# Periph.net
KiCad netlist of a schematic drawn in Altium Designer
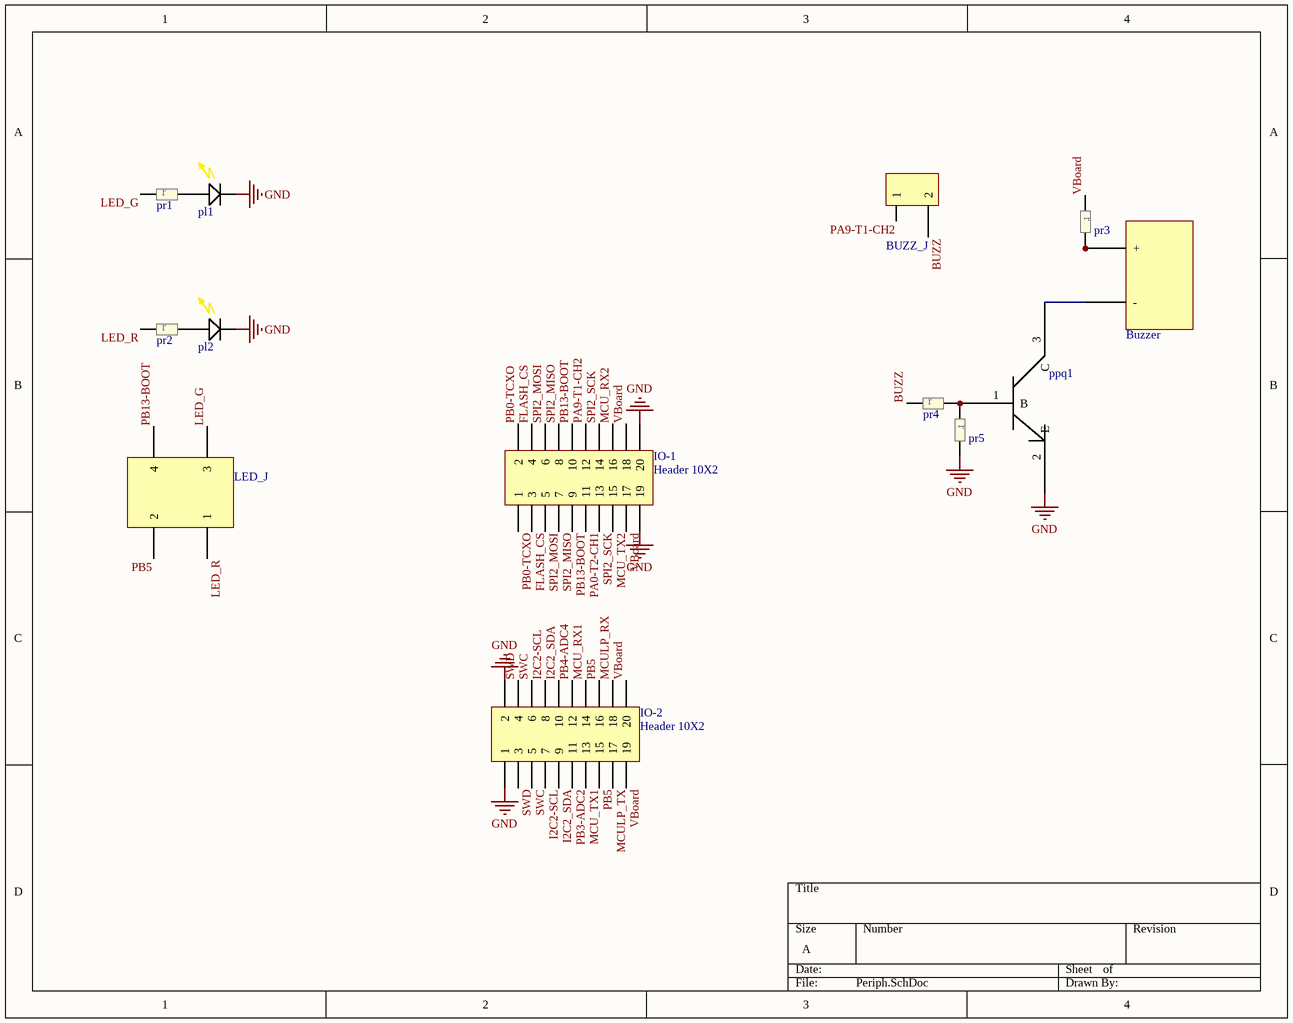
[diagram p0: Periph.SchDoc]

(export (version "E")
  (design (tool "Eeschema 10.0.6"))
  (components
    (comp (ref "Buzzer")
      (value "LED")
      (footprint "ABR_BUZZER_9MM_3D")
      (libsource (lib "abr_led_dip") (part "abr_buzzer"))
    )
    (comp (ref "BUZZ_J")
      (value "pin header 2mm")
      (footprint "abr_ph_2x1_2mm_3d_male")
      (libsource (lib "abr_ph_2mm_96_02") (part "abr_2x1_2mm"))
    )
    (comp (ref "IO-1")
      (value "Header 10X2")
      (footprint "HDR2X10")
      (description "Header, 10-Pin, Dual row")
      (fields (field (name "PUBLISHER") "Altium Limited"))
      (libsource (lib "Miscellaneous Connectors") (part "Header 10X2"))
    )
    (comp (ref "IO-2")
      (value "Header 10X2")
      (footprint "HDR2X10")
      (description "Header, 10-Pin, Dual row")
      (fields (field (name "PUBLISHER") "Altium Limited"))
      (libsource (lib "Miscellaneous Connectors") (part "Header 10X2"))
    )
    (comp (ref "LED_J")
      (value "pin header 2mm")
      (footprint "abr_ph_2x2_2mm_3d_male")
      (libsource (lib "abr_ph_2mm_96_02") (part "abr_2x2_2mm"))
    )
    (comp (ref "pl1")
      (value "smd-0805")
      (footprint "abr_led_g_0805_3d")
      (libsource (lib "abr_smd_0805_all") (part "abr_led_0805"))
    )
    (comp (ref "pl2")
      (value "smd-0805")
      (footprint "abr_led_r_0805_3d")
      (libsource (lib "abr_smd_0805_all") (part "abr_led_0805"))
    )
    (comp (ref "ppq1")
      (value "transistor")
      (footprint "abr_fp_sot-23_3d")
      (libsource (lib "abr_transistor_smd") (part "abr_bc847"))
    )
    (comp (ref "pr1")
      (value "2.2K")
      (footprint "abr_res_0805_3d")
      (libsource (lib "") (part "abr_res_0805_1"))
    )
    (comp (ref "pr2")
      (value "2.2K")
      (footprint "abr_res_0805_3d")
      (libsource (lib "") (part "abr_res_0805_1"))
    )
    (comp (ref "pr3")
      (value "2.2K")
      (footprint "abr_res_0805_3d")
      (libsource (lib "abr_smd_0805_all") (part "abr_res_0805"))
    )
    (comp (ref "pr4")
      (value "2.2K")
      (footprint "abr_res_0805_3d")
      (libsource (lib "") (part "abr_res_0805_1"))
    )
    (comp (ref "pr5")
      (value "2.2K")
      (footprint "abr_res_0805_3d")
      (libsource (lib "abr_smd_0805_all") (part "abr_res_0805"))
    )
  )
  (nets
    (net (code "1") (name "/BUZZ") (class "Default")
      (node (ref "BUZZ_J") (pin "2") (pinfunction "2_2") (pintype "passive"))
      (node (ref "pr4") (pin "0") (pinfunction "0_0") (pintype "passive"))
    )
    (net (code "2") (name "/FLASH_CS") (class "Default")
      (node (ref "IO-1") (pin "3") (pinfunction "3_3") (pintype "passive"))
      (node (ref "IO-1") (pin "4") (pinfunction "4_4") (pintype "passive"))
    )
    (net (code "3") (name "/I2C2-SCL") (class "Default")
      (node (ref "IO-2") (pin "7") (pinfunction "7_7") (pintype "passive"))
      (node (ref "IO-2") (pin "8") (pinfunction "8_8") (pintype "passive"))
    )
    (net (code "4") (name "/I2C2_SDA") (class "Default")
      (node (ref "IO-2") (pin "10") (pinfunction "10_10") (pintype "passive"))
      (node (ref "IO-2") (pin "9") (pinfunction "9_9") (pintype "passive"))
    )
    (net (code "5") (name "/LED_G") (class "Default")
      (node (ref "LED_J") (pin "3") (pinfunction "3_3") (pintype "passive"))
      (node (ref "pr1") (pin "0") (pinfunction "0_0") (pintype "passive"))
    )
    (net (code "6") (name "/LED_R") (class "Default")
      (node (ref "LED_J") (pin "1") (pinfunction "1_1") (pintype "passive"))
      (node (ref "pr2") (pin "0") (pinfunction "0_0") (pintype "passive"))
    )
    (net (code "7") (name "/MCULP_RX") (class "Default")
      (node (ref "IO-2") (pin "18") (pinfunction "18_18") (pintype "passive"))
    )
    (net (code "8") (name "/MCULP_TX") (class "Default")
      (node (ref "IO-2") (pin "17") (pinfunction "17_17") (pintype "passive"))
    )
    (net (code "9") (name "/MCU_RX1") (class "Default")
      (node (ref "IO-2") (pin "14") (pinfunction "14_14") (pintype "passive"))
    )
    (net (code "10") (name "/MCU_RX2") (class "Default")
      (node (ref "IO-1") (pin "16") (pinfunction "16_16") (pintype "passive"))
    )
    (net (code "11") (name "/MCU_TX1") (class "Default")
      (node (ref "IO-2") (pin "13") (pinfunction "13_13") (pintype "passive"))
    )
    (net (code "12") (name "/MCU_TX2") (class "Default")
      (node (ref "IO-1") (pin "15") (pinfunction "15_15") (pintype "passive"))
    )
    (net (code "13") (name "/PA0-T2-CH1") (class "Default")
      (node (ref "IO-1") (pin "11") (pinfunction "11_11") (pintype "passive"))
    )
    (net (code "14") (name "/PA9-T1-CH2") (class "Default")
      (node (ref "BUZZ_J") (pin "1") (pinfunction "1_1") (pintype "passive"))
      (node (ref "IO-1") (pin "12") (pinfunction "12_12") (pintype "passive"))
    )
    (net (code "15") (name "/PB0-TCXO") (class "Default")
      (node (ref "IO-1") (pin "1") (pinfunction "1_1") (pintype "passive"))
      (node (ref "IO-1") (pin "2") (pinfunction "2_2") (pintype "passive"))
    )
    (net (code "16") (name "/PB3-ADC2") (class "Default")
      (node (ref "IO-2") (pin "11") (pinfunction "11_11") (pintype "passive"))
    )
    (net (code "17") (name "/PB4-ADC4") (class "Default")
      (node (ref "IO-2") (pin "12") (pinfunction "12_12") (pintype "passive"))
    )
    (net (code "18") (name "/PB5") (class "Default")
      (node (ref "IO-2") (pin "15") (pinfunction "15_15") (pintype "passive"))
      (node (ref "IO-2") (pin "16") (pinfunction "16_16") (pintype "passive"))
      (node (ref "LED_J") (pin "2") (pinfunction "2_2") (pintype "passive"))
    )
    (net (code "19") (name "/PB13-BOOT") (class "Default")
      (node (ref "IO-1") (pin "10") (pinfunction "10_10") (pintype "passive"))
      (node (ref "IO-1") (pin "9") (pinfunction "9_9") (pintype "passive"))
      (node (ref "LED_J") (pin "4") (pinfunction "4_4") (pintype "passive"))
    )
    (net (code "20") (name "/SPI2_MISO") (class "Default")
      (node (ref "IO-1") (pin "7") (pinfunction "7_7") (pintype "passive"))
      (node (ref "IO-1") (pin "8") (pinfunction "8_8") (pintype "passive"))
    )
    (net (code "21") (name "/SPI2_MOSI") (class "Default")
      (node (ref "IO-1") (pin "5") (pinfunction "5_5") (pintype "passive"))
      (node (ref "IO-1") (pin "6") (pinfunction "6_6") (pintype "passive"))
    )
    (net (code "22") (name "/SPI2_SCK") (class "Default")
      (node (ref "IO-1") (pin "13") (pinfunction "13_13") (pintype "passive"))
      (node (ref "IO-1") (pin "14") (pinfunction "14_14") (pintype "passive"))
    )
    (net (code "23") (name "/SWC") (class "Default")
      (node (ref "IO-2") (pin "5") (pinfunction "5_5") (pintype "passive"))
      (node (ref "IO-2") (pin "6") (pinfunction "6_6") (pintype "passive"))
    )
    (net (code "24") (name "/SWD") (class "Default")
      (node (ref "IO-2") (pin "3") (pinfunction "3_3") (pintype "passive"))
      (node (ref "IO-2") (pin "4") (pinfunction "4_4") (pintype "passive"))
    )
    (net (code "25") (name "/VBoard") (class "Default")
      (node (ref "IO-1") (pin "17") (pinfunction "17_17") (pintype "passive"))
      (node (ref "IO-1") (pin "18") (pinfunction "18_18") (pintype "passive"))
      (node (ref "IO-2") (pin "19") (pinfunction "19_19") (pintype "passive"))
      (node (ref "IO-2") (pin "20") (pinfunction "20_20") (pintype "passive"))
      (node (ref "pr3") (pin "0") (pinfunction "0_0") (pintype "passive"))
    )
    (net (code "26") (name "GND") (class "Default")
      (node (ref "IO-1") (pin "19") (pinfunction "19_19") (pintype "passive"))
      (node (ref "IO-1") (pin "20") (pinfunction "20_20") (pintype "passive"))
      (node (ref "IO-2") (pin "1") (pinfunction "1_1") (pintype "passive"))
      (node (ref "IO-2") (pin "2") (pinfunction "2_2") (pintype "passive"))
      (node (ref "pl1") (pin "1") (pinfunction "1_1") (pintype "passive"))
      (node (ref "pl2") (pin "1") (pinfunction "1_1") (pintype "passive"))
      (node (ref "ppq1") (pin "2") (pinfunction "E_2") (pintype "passive"))
      (node (ref "pr5") (pin "1") (pinfunction "0_1") (pintype "passive"))
    )
    (net (code "27") (name "Net-(Buzzer-+)") (class "Default")
      (node (ref "Buzzer") (pin "1") (pinfunction "+_1") (pintype "passive"))
      (node (ref "pr3") (pin "1") (pinfunction "0_1") (pintype "passive"))
    )
    (net (code "28") (name "Net-(Buzzer--)") (class "Default")
      (node (ref "Buzzer") (pin "2") (pinfunction "-_2") (pintype "passive"))
      (node (ref "ppq1") (pin "3") (pinfunction "C_3") (pintype "passive"))
    )
    (net (code "29") (name "Net-(pl1-15)") (class "Default")
      (node (ref "pl1") (pin "0") (pinfunction "15_0") (pintype "passive"))
      (node (ref "pr1") (pin "1") (pinfunction "0_1") (pintype "passive"))
    )
    (net (code "30") (name "Net-(pl2-15)") (class "Default")
      (node (ref "pl2") (pin "0") (pinfunction "15_0") (pintype "passive"))
      (node (ref "pr2") (pin "1") (pinfunction "0_1") (pintype "passive"))
    )
    (net (code "31") (name "Net-(ppq1-B)") (class "Default")
      (node (ref "ppq1") (pin "1") (pinfunction "B_1") (pintype "passive"))
      (node (ref "pr4") (pin "1") (pinfunction "0_1") (pintype "passive"))
      (node (ref "pr5") (pin "0") (pinfunction "0_0") (pintype "passive"))
    )
  )
)
